# 03_Power_Switch.net
KiCad netlist of a schematic drawn in Altium Designer
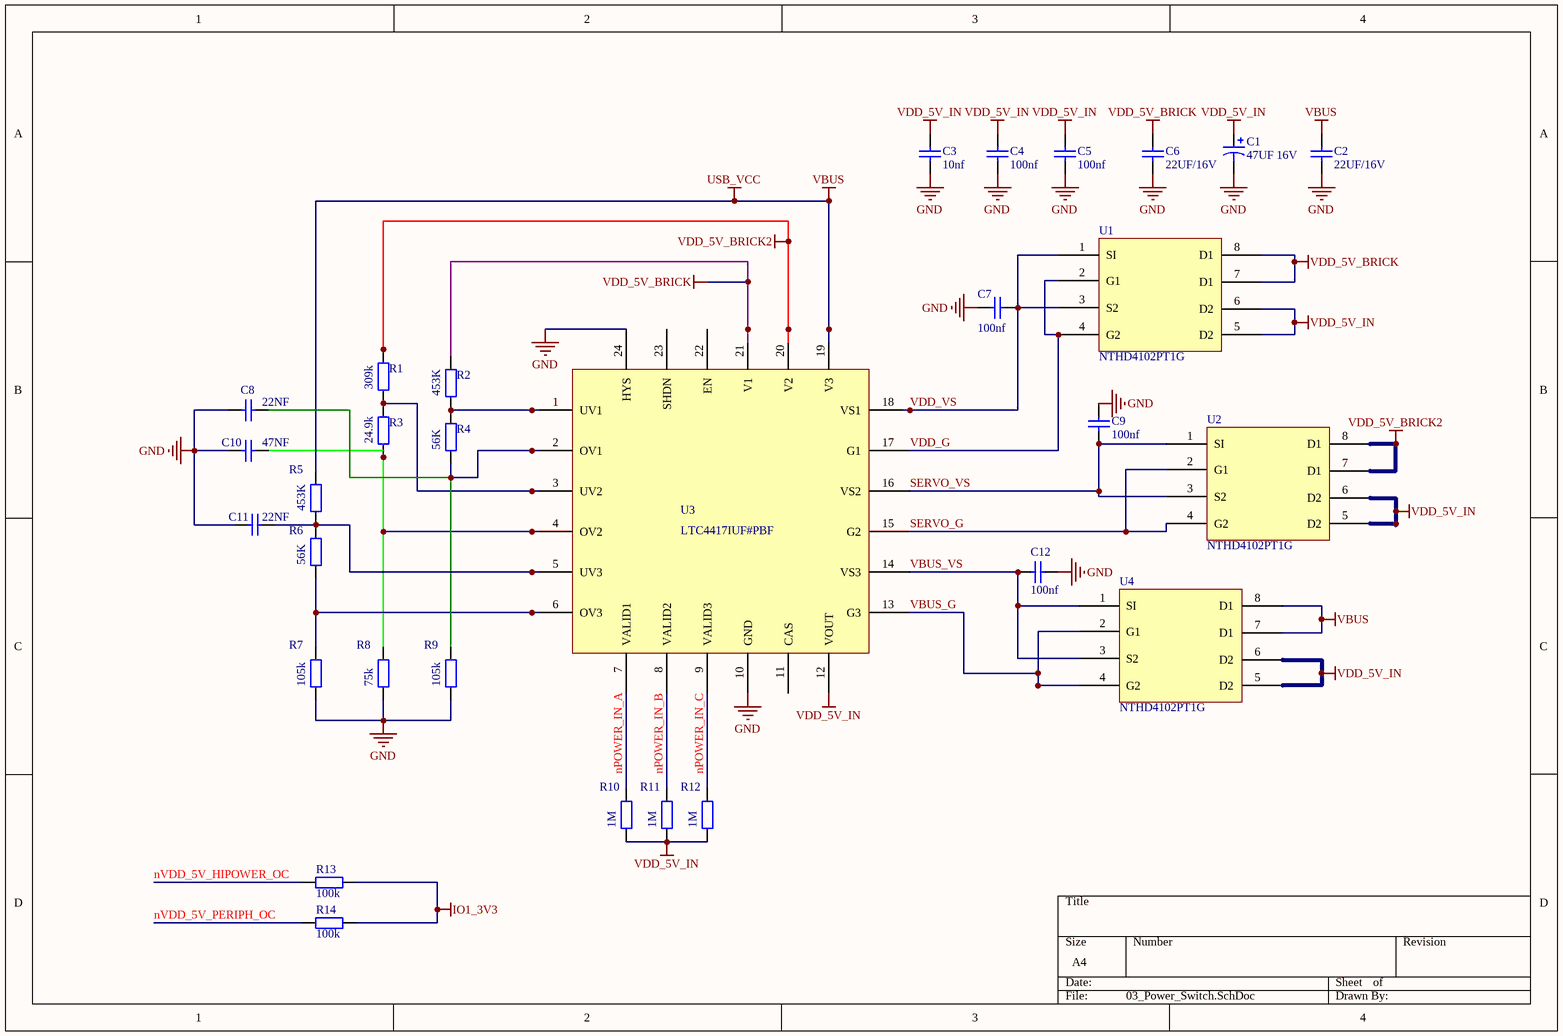
[diagram p0: 03_Power_Switch.SchDoc]

(export (version "E")
  (design (tool "Eeschema 10.0.6"))
  (components
    (comp (ref "C1")
      (value "47UF 16V")
      (footprint "7343CAP")
      (description "Polarized Capacitor (Radial)")
      (fields (field (name "PUBLISHER") "Altium Limited"))
      (libsource (lib "Miscellaneous Devices") (part "Cap Pol1"))
    )
    (comp (ref "C2")
      (value "22UF/16V")
      (fields (field (name "PUBLISHER") "Altium Limited"))
      (libsource (lib "Miscellaneous Devices") (part "Cap"))
    )
    (comp (ref "C3")
      (value "10nf")
      (fields (field (name "PUBLISHER") "Altium Limited"))
      (libsource (lib "Miscellaneous Devices") (part "Cap"))
    )
    (comp (ref "C4")
      (value "100nf")
      (fields (field (name "PUBLISHER") "Altium Limited"))
      (libsource (lib "Miscellaneous Devices") (part "Cap"))
    )
    (comp (ref "C5")
      (value "100nf")
      (fields (field (name "PUBLISHER") "Altium Limited"))
      (libsource (lib "Miscellaneous Devices") (part "Cap"))
    )
    (comp (ref "C6")
      (value "22UF/16V")
      (fields (field (name "PUBLISHER") "Altium Limited"))
      (libsource (lib "Miscellaneous Devices") (part "Cap"))
    )
    (comp (ref "C7")
      (value "100nf")
      (fields (field (name "PUBLISHER") "Altium Limited"))
      (libsource (lib "Miscellaneous Devices") (part "Cap"))
    )
    (comp (ref "C8")
      (value "22NF")
      (fields (field (name "PUBLISHER") "Altium Limited"))
      (libsource (lib "Miscellaneous Devices") (part "Cap"))
    )
    (comp (ref "C9")
      (value "100nf")
      (fields (field (name "PUBLISHER") "Altium Limited"))
      (libsource (lib "Miscellaneous Devices") (part "Cap"))
    )
    (comp (ref "C10")
      (value "47NF")
      (fields (field (name "PUBLISHER") "Altium Limited"))
      (libsource (lib "Miscellaneous Devices") (part "Cap"))
    )
    (comp (ref "C11")
      (value "22NF")
      (fields (field (name "PUBLISHER") "Altium Limited"))
      (libsource (lib "Miscellaneous Devices") (part "Cap"))
    )
    (comp (ref "C12")
      (value "100nf")
      (fields (field (name "PUBLISHER") "Altium Limited"))
      (libsource (lib "Miscellaneous Devices") (part "Cap"))
    )
    (comp (ref "R1")
      (value "309k")
      (description "Resistor")
      (fields (field (name "PUBLISHER") "Altium Limited"))
      (libsource (lib "Miscellaneous Devices") (part "Res2"))
    )
    (comp (ref "R2")
      (value "453K")
      (description "Resistor")
      (fields (field (name "PUBLISHER") "Altium Limited"))
      (libsource (lib "Miscellaneous Devices") (part "Res2"))
    )
    (comp (ref "R3")
      (value "24.9k")
      (description "Resistor")
      (fields (field (name "PUBLISHER") "Altium Limited"))
      (libsource (lib "Miscellaneous Devices") (part "Res2"))
    )
    (comp (ref "R4")
      (value "56K")
      (description "Resistor")
      (fields (field (name "PUBLISHER") "Altium Limited"))
      (libsource (lib "Miscellaneous Devices") (part "Res2"))
    )
    (comp (ref "R5")
      (value "453K")
      (description "Resistor")
      (fields (field (name "PUBLISHER") "Altium Limited"))
      (libsource (lib "Miscellaneous Devices") (part "Res2"))
    )
    (comp (ref "R6")
      (value "56K")
      (description "Resistor")
      (fields (field (name "PUBLISHER") "Altium Limited"))
      (libsource (lib "Miscellaneous Devices") (part "Res2"))
    )
    (comp (ref "R7")
      (value "105k")
      (description "Resistor")
      (fields (field (name "PUBLISHER") "Altium Limited"))
      (libsource (lib "Miscellaneous Devices") (part "Res2"))
    )
    (comp (ref "R8")
      (value "75k")
      (description "Resistor")
      (fields (field (name "PUBLISHER") "Altium Limited"))
      (libsource (lib "Miscellaneous Devices") (part "Res2"))
    )
    (comp (ref "R9")
      (value "105k")
      (description "Resistor")
      (fields (field (name "PUBLISHER") "Altium Limited"))
      (libsource (lib "Miscellaneous Devices") (part "Res2"))
    )
    (comp (ref "R10")
      (value "1M")
      (description "Resistor")
      (fields (field (name "PUBLISHER") "Altium Limited"))
      (libsource (lib "Miscellaneous Devices") (part "Res2"))
    )
    (comp (ref "R11")
      (value "1M")
      (description "Resistor")
      (fields (field (name "PUBLISHER") "Altium Limited"))
      (libsource (lib "Miscellaneous Devices") (part "Res2"))
    )
    (comp (ref "R12")
      (value "1M")
      (description "Resistor")
      (fields (field (name "PUBLISHER") "Altium Limited"))
      (libsource (lib "Miscellaneous Devices") (part "Res2"))
    )
    (comp (ref "R13")
      (value "100k")
      (description "Resistor")
      (fields (field (name "PUBLISHER") "Altium Limited"))
      (libsource (lib "") (part "Res2_1"))
    )
    (comp (ref "R14")
      (value "100k")
      (description "Resistor")
      (fields (field (name "PUBLISHER") "Altium Limited"))
      (libsource (lib "") (part "Res2_1"))
    )
    (comp (ref "U1")
      (value "NTHD4102PT1G")
      (footprint "1206-8")
      (libsource (lib "hack") (part "NTHD4102PT1G"))
    )
    (comp (ref "U2")
      (value "NTHD4102PT1G")
      (footprint "1206-8")
      (libsource (lib "hack") (part "NTHD4102PT1G"))
    )
    (comp (ref "U3")
      (value "LTC4417IUF#PBF")
      (footprint "QFN24")
      (libsource (lib "hack") (part "LTC4417IUF#PBF"))
    )
    (comp (ref "U4")
      (value "NTHD4102PT1G")
      (footprint "1206-8")
      (libsource (lib "hack") (part "NTHD4102PT1G"))
    )
  )
  (nets
    (net (code "1") (name "/SERVO_G") (class "Default")
      (node (ref "U2") (pin "2") (pinfunction "G1_2") (pintype "passive"))
      (node (ref "U2") (pin "4") (pinfunction "G2_4") (pintype "passive"))
      (node (ref "U3") (pin "15") (pinfunction "G2_15") (pintype "passive"))
    )
    (net (code "2") (name "/SERVO_VS") (class "Default")
      (node (ref "C9") (pin "1") (pinfunction "1_1") (pintype "passive"))
      (node (ref "U2") (pin "1") (pinfunction "SI_1") (pintype "passive"))
      (node (ref "U2") (pin "3") (pinfunction "S2_3") (pintype "passive"))
      (node (ref "U3") (pin "16") (pinfunction "VS2_16") (pintype "passive"))
    )
    (net (code "3") (name "/VBUS_G") (class "Default")
      (node (ref "U3") (pin "13") (pinfunction "G3_13") (pintype "passive"))
      (node (ref "U4") (pin "2") (pinfunction "G1_2") (pintype "passive"))
      (node (ref "U4") (pin "4") (pinfunction "G2_4") (pintype "passive"))
    )
    (net (code "4") (name "/VBUS_VS") (class "Default")
      (node (ref "C12") (pin "1") (pinfunction "1_1") (pintype "passive"))
      (node (ref "U3") (pin "14") (pinfunction "VS3_14") (pintype "passive"))
      (node (ref "U4") (pin "1") (pinfunction "SI_1") (pintype "passive"))
      (node (ref "U4") (pin "3") (pinfunction "S2_3") (pintype "passive"))
    )
    (net (code "5") (name "/VDD_G") (class "Default")
      (node (ref "U1") (pin "2") (pinfunction "G1_2") (pintype "passive"))
      (node (ref "U1") (pin "4") (pinfunction "G2_4") (pintype "passive"))
      (node (ref "U3") (pin "17") (pinfunction "G1_17") (pintype "passive"))
    )
    (net (code "6") (name "/VDD_VS") (class "Default")
      (node (ref "C7") (pin "1") (pinfunction "1_1") (pintype "passive"))
      (node (ref "U1") (pin "1") (pinfunction "SI_1") (pintype "passive"))
      (node (ref "U1") (pin "3") (pinfunction "S2_3") (pintype "passive"))
      (node (ref "U3") (pin "18") (pinfunction "VS1_18") (pintype "passive"))
    )
    (net (code "7") (name "/nPOWER_IN_A") (class "Default")
      (node (ref "R10") (pin "2") (pinfunction "2_2") (pintype "passive"))
      (node (ref "U3") (pin "7") (pinfunction "VALID1_7") (pintype "passive"))
    )
    (net (code "8") (name "/nPOWER_IN_B") (class "Default")
      (node (ref "R11") (pin "2") (pinfunction "2_2") (pintype "passive"))
      (node (ref "U3") (pin "8") (pinfunction "VALID2_8") (pintype "passive"))
    )
    (net (code "9") (name "/nPOWER_IN_C") (class "Default")
      (node (ref "R12") (pin "2") (pinfunction "2_2") (pintype "passive"))
      (node (ref "U3") (pin "9") (pinfunction "VALID3_9") (pintype "passive"))
    )
    (net (code "10") (name "/nVDD_5V_HIPOWER_OC") (class "Default")
      (node (ref "R13") (pin "1") (pinfunction "1_1") (pintype "passive"))
    )
    (net (code "11") (name "/nVDD_5V_PERIPH_OC") (class "Default")
      (node (ref "R14") (pin "1") (pinfunction "1_1") (pintype "passive"))
    )
    (net (code "12") (name "GND") (class "Default")
      (node (ref "C1") (pin "C") (pinfunction "2_C") (pintype "passive"))
      (node (ref "C10") (pin "2") (pinfunction "2_2") (pintype "passive"))
      (node (ref "C11") (pin "2") (pinfunction "2_2") (pintype "passive"))
      (node (ref "C12") (pin "2") (pinfunction "2_2") (pintype "passive"))
      (node (ref "C2") (pin "1") (pinfunction "1_1") (pintype "passive"))
      (node (ref "C3") (pin "1") (pinfunction "1_1") (pintype "passive"))
      (node (ref "C4") (pin "1") (pinfunction "1_1") (pintype "passive"))
      (node (ref "C5") (pin "1") (pinfunction "1_1") (pintype "passive"))
      (node (ref "C6") (pin "1") (pinfunction "1_1") (pintype "passive"))
      (node (ref "C7") (pin "2") (pinfunction "2_2") (pintype "passive"))
      (node (ref "C8") (pin "2") (pinfunction "2_2") (pintype "passive"))
      (node (ref "C9") (pin "2") (pinfunction "2_2") (pintype "passive"))
      (node (ref "R7") (pin "1") (pinfunction "1_1") (pintype "passive"))
      (node (ref "R8") (pin "1") (pinfunction "1_1") (pintype "passive"))
      (node (ref "R9") (pin "1") (pinfunction "1_1") (pintype "passive"))
      (node (ref "U3") (pin "10") (pinfunction "GND_10") (pintype "passive"))
      (node (ref "U3") (pin "24") (pinfunction "HYS_24") (pintype "passive"))
    )
    (net (code "13") (name "IO1_3V3") (class "Default")
      (node (ref "R13") (pin "2") (pinfunction "2_2") (pintype "passive"))
      (node (ref "R14") (pin "2") (pinfunction "2_2") (pintype "passive"))
    )
    (net (code "14") (name "Net-(U3-OV1)") (class "Default")
      (node (ref "C8") (pin "1") (pinfunction "1_1") (pintype "passive"))
      (node (ref "R4") (pin "1") (pinfunction "1_1") (pintype "passive"))
      (node (ref "R9") (pin "2") (pinfunction "2_2") (pintype "passive"))
      (node (ref "U3") (pin "2") (pinfunction "OV1_2") (pintype "passive"))
    )
    (net (code "15") (name "Net-(U3-OV2)") (class "Default")
      (node (ref "C10") (pin "1") (pinfunction "1_1") (pintype "passive"))
      (node (ref "R3") (pin "1") (pinfunction "1_1") (pintype "passive"))
      (node (ref "R8") (pin "2") (pinfunction "2_2") (pintype "passive"))
      (node (ref "U3") (pin "4") (pinfunction "OV2_4") (pintype "passive"))
    )
    (net (code "16") (name "Net-(U3-OV3)") (class "Default")
      (node (ref "R6") (pin "1") (pinfunction "1_1") (pintype "passive"))
      (node (ref "R7") (pin "2") (pinfunction "2_2") (pintype "passive"))
      (node (ref "U3") (pin "6") (pinfunction "OV3_6") (pintype "passive"))
    )
    (net (code "17") (name "Net-(U3-UV1)") (class "Default")
      (node (ref "R2") (pin "1") (pinfunction "1_1") (pintype "passive"))
      (node (ref "R4") (pin "2") (pinfunction "2_2") (pintype "passive"))
      (node (ref "U3") (pin "1") (pinfunction "UV1_1") (pintype "passive"))
    )
    (net (code "18") (name "Net-(U3-UV2)") (class "Default")
      (node (ref "R1") (pin "1") (pinfunction "1_1") (pintype "passive"))
      (node (ref "R3") (pin "2") (pinfunction "2_2") (pintype "passive"))
      (node (ref "U3") (pin "3") (pinfunction "UV2_3") (pintype "passive"))
    )
    (net (code "19") (name "Net-(U3-UV3)") (class "Default")
      (node (ref "C11") (pin "1") (pinfunction "1_1") (pintype "passive"))
      (node (ref "R5") (pin "1") (pinfunction "1_1") (pintype "passive"))
      (node (ref "R6") (pin "2") (pinfunction "2_2") (pintype "passive"))
      (node (ref "U3") (pin "5") (pinfunction "UV3_5") (pintype "passive"))
    )
    (net (code "20") (name "USB_VCC") (class "Default")
      (node (ref "C2") (pin "2") (pinfunction "2_2") (pintype "passive"))
      (node (ref "R5") (pin "2") (pinfunction "2_2") (pintype "passive"))
      (node (ref "U3") (pin "19") (pinfunction "V3_19") (pintype "passive"))
      (node (ref "U4") (pin "7") (pinfunction "D1_7") (pintype "passive"))
      (node (ref "U4") (pin "8") (pinfunction "D1_8") (pintype "passive"))
    )
    (net (code "21") (name "VDD_5V_BRICK") (class "Default")
      (node (ref "C6") (pin "2") (pinfunction "2_2") (pintype "passive"))
      (node (ref "R2") (pin "2") (pinfunction "2_2") (pintype "passive"))
      (node (ref "U1") (pin "7") (pinfunction "D1_7") (pintype "passive"))
      (node (ref "U1") (pin "8") (pinfunction "D1_8") (pintype "passive"))
      (node (ref "U3") (pin "21") (pinfunction "V1_21") (pintype "passive"))
    )
    (net (code "22") (name "VDD_5V_BRICK2") (class "Default")
      (node (ref "R1") (pin "2") (pinfunction "2_2") (pintype "passive"))
      (node (ref "U2") (pin "7") (pinfunction "D1_7") (pintype "passive"))
      (node (ref "U2") (pin "8") (pinfunction "D1_8") (pintype "passive"))
      (node (ref "U3") (pin "20") (pinfunction "V2_20") (pintype "passive"))
    )
    (net (code "23") (name "VDD_5V_IN") (class "Default")
      (node (ref "C1") (pin "A") (pinfunction "1_A") (pintype "passive"))
      (node (ref "C3") (pin "2") (pinfunction "2_2") (pintype "passive"))
      (node (ref "C4") (pin "2") (pinfunction "2_2") (pintype "passive"))
      (node (ref "C5") (pin "2") (pinfunction "2_2") (pintype "passive"))
      (node (ref "R10") (pin "1") (pinfunction "1_1") (pintype "passive"))
      (node (ref "R11") (pin "1") (pinfunction "1_1") (pintype "passive"))
      (node (ref "R12") (pin "1") (pinfunction "1_1") (pintype "passive"))
      (node (ref "U1") (pin "5") (pinfunction "D2_5") (pintype "passive"))
      (node (ref "U1") (pin "6") (pinfunction "D2_6") (pintype "passive"))
      (node (ref "U2") (pin "5") (pinfunction "D2_5") (pintype "passive"))
      (node (ref "U2") (pin "6") (pinfunction "D2_6") (pintype "passive"))
      (node (ref "U3") (pin "12") (pinfunction "VOUT_12") (pintype "passive"))
      (node (ref "U4") (pin "5") (pinfunction "D2_5") (pintype "passive"))
      (node (ref "U4") (pin "6") (pinfunction "D2_6") (pintype "passive"))
    )
    (net (code "24") (name "unconnected-(U3-CAS-Pad11)") (class "Default")
      (node (ref "U3") (pin "11") (pinfunction "CAS_11") (pintype "passive"))
    )
    (net (code "25") (name "unconnected-(U3-EN-Pad22)") (class "Default")
      (node (ref "U3") (pin "22") (pinfunction "EN_22") (pintype "passive"))
    )
    (net (code "26") (name "unconnected-(U3-SHDN-Pad23)") (class "Default")
      (node (ref "U3") (pin "23") (pinfunction "SHDN_23") (pintype "passive"))
    )
  )
)
